# BluetoothHID.net
KiCad netlist of a schematic drawn in Altium Designer
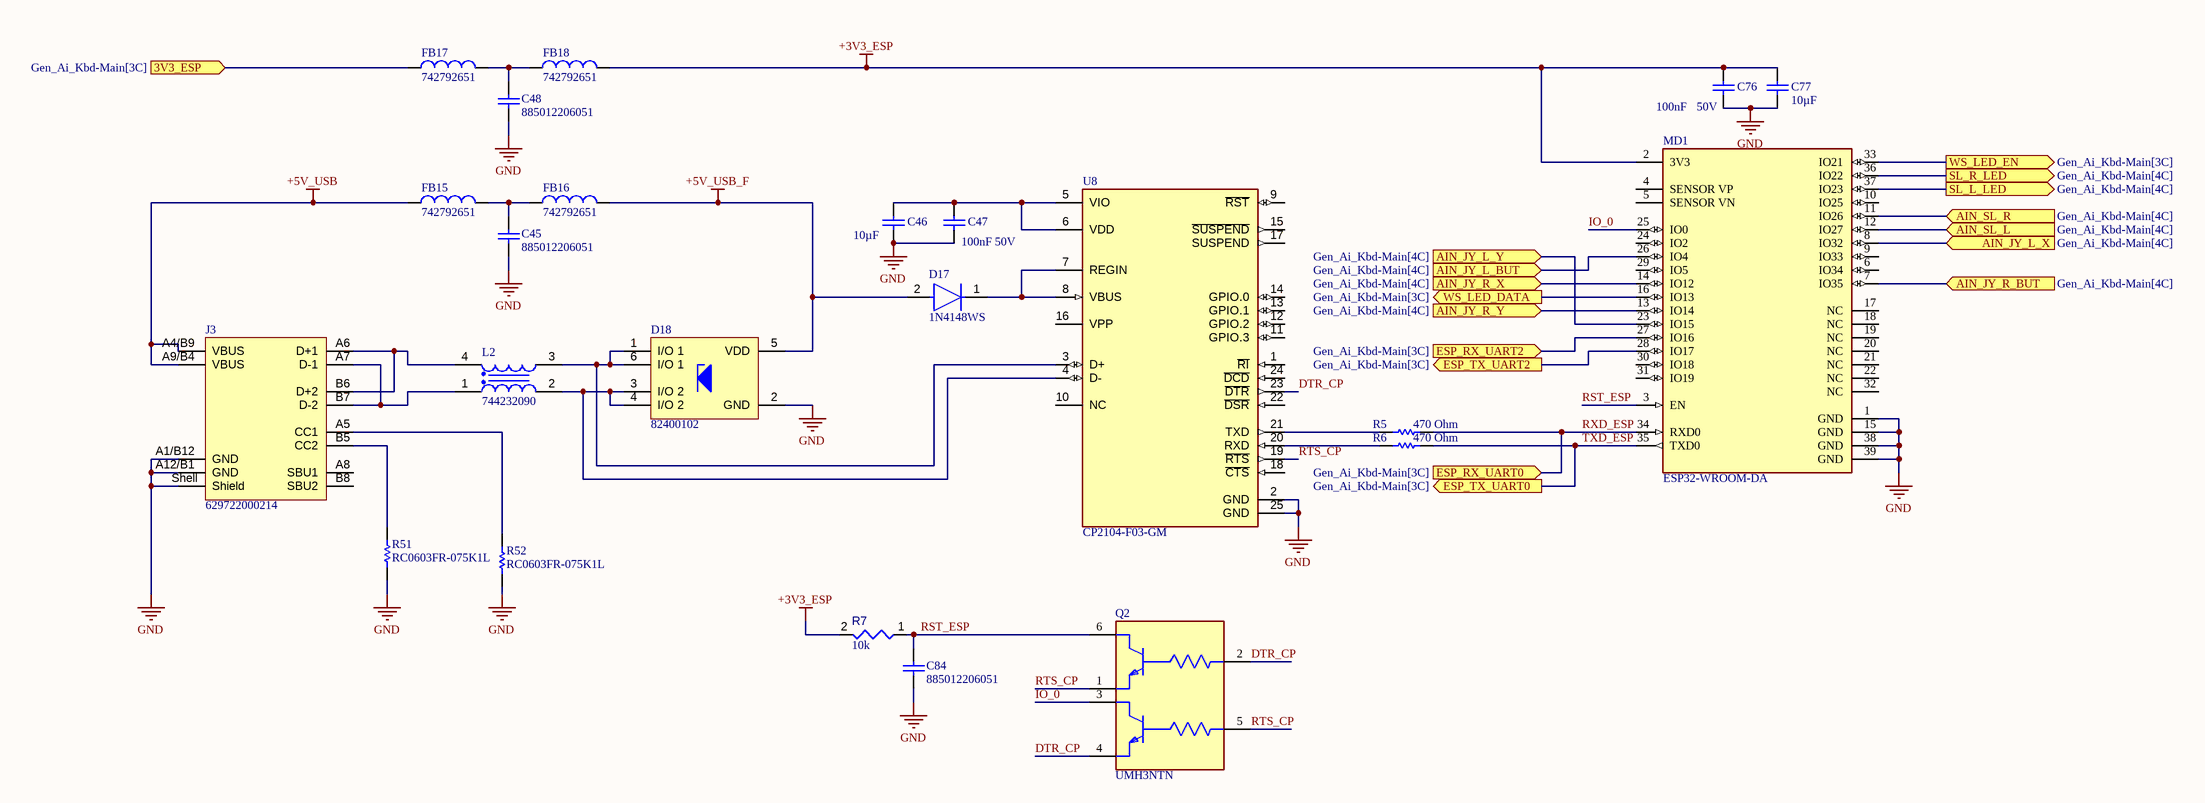
[diagram p0: BluetoothHID.SchDoc]

(export (version "E")
  (design (tool "Eeschema 10.0.6"))
  (components
    (comp (ref "C45")
      (value "885012206051")
      (footprint "WCAP-CSGP_0603_L1.6W0.8H0.8_Reflow")
      (description "885012206051 Cap Cer 0.68UF 16V X7R 0603")
      (fields (field (name "TOLERANCE") "10%"))
      (libsource (lib "Altium Content Vault") (part "Capacitor_Non-Polarized"))
    )
    (comp (ref "C46")
      (value "885012106006")
      (footprint "WCAP-CSGP_0603_L1.6W0.8H0.8_Reflow")
      (description "WCAP-CSGP Multilayer Ceramic Chip Capacitor, General Purpose, size 0603, X5R, 10µF, 6.3VDC")
      (fields (field (name "MANUFACTURER") "Wurth Elektronik") (field (name "CAPACITANCE") "10µF"))
      (libsource (lib "Test365") (part "885012209047R"))
    )
    (comp (ref "C47")
      (value "885012206095")
      (footprint "WCAP-CSGP_0603_L1.6W0.8H0.8_Reflow")
      (description "WCAP-CSGP Multilayer Ceramic Chip Capacitor, General Purpose, size 0603, X7R, 100nF, 50VDC")
      (fields
        (field (name "CAPACITANCE") "100nF")
        (field (name "MANUFACTURER") "Wurth Elektronik")
        (field (name "RATED VOLTAGE (DC)") "50V")
      )
      (libsource (lib "Test365") (part "885012209047R"))
    )
    (comp (ref "C48")
      (value "885012206051")
      (footprint "WCAP-CSGP_0603_L1.6W0.8H0.8_Reflow")
      (description "885012206051 Cap Cer 0.68UF 16V X7R 0603")
      (fields (field (name "TOLERANCE") "10%"))
      (libsource (lib "Altium Content Vault") (part "Capacitor_Non-Polarized"))
    )
    (comp (ref "C76")
      (value "885012206095")
      (footprint "WCAP-CSGP_0603_L1.6W0.8H0.8_Reflow")
      (description "WCAP-CSGP Multilayer Ceramic Chip Capacitor, General Purpose, size 0603, X7R, 100nF, 50VDC")
      (fields
        (field (name "CAPACITANCE") "100nF")
        (field (name "MANUFACTURER") "Wurth Elektronik")
        (field (name "RATED VOLTAGE (DC)") "50V")
      )
      (libsource (lib "Test365") (part "885012209047R"))
    )
    (comp (ref "C77")
      (value "885012106006")
      (footprint "WCAP-CSGP_0603_L1.6W0.8H0.8_Reflow")
      (description "WCAP-CSGP Multilayer Ceramic Chip Capacitor, General Purpose, size 0603, X5R, 10µF, 6.3VDC")
      (fields (field (name "MANUFACTURER") "Wurth Elektronik") (field (name "CAPACITANCE") "10µF"))
      (libsource (lib "Test365") (part "885012209047R"))
    )
    (comp (ref "C84")
      (value "885012206051")
      (footprint "WCAP-CSGP_0603_L1.6W0.8H0.8_Reflow")
      (description "885012206051 Cap Cer 0.68UF 16V X7R 0603")
      (fields (field (name "TOLERANCE") "10%"))
      (libsource (lib "Altium Content Vault") (part "Capacitor_Non-Polarized"))
    )
    (comp (ref "D17")
      (value "1N4148WS")
      (footprint "FP-477AB-IPC_C")
      (description "DIODE GEN PURP 75V 150MA SOD323F")
      (libsource (lib "Altium Content Vault") (part "d7152d700b627762746794eb795d46e"))
    )
    (comp (ref "D18")
      (value "82400102")
      (footprint "WE-TVS_SOT23-6L")
      (libsource (lib "Altium Content Vault") (part "Diode_2+1 Channel_Unidirectional - 82400102"))
    )
    (comp (ref "FB15")
      (value "742792651")
      (footprint "WE-CBF_0603_L1.6W0.8H0.8_HC")
      (fields (field (name "TOLERANCE") "25%"))
      (libsource (lib "Altium Content Vault") (part "Ferrite"))
    )
    (comp (ref "FB16")
      (value "742792651")
      (footprint "WE-CBF_0603_L1.6W0.8H0.8_HC")
      (fields (field (name "TOLERANCE") "25%"))
      (libsource (lib "Altium Content Vault") (part "Ferrite"))
    )
    (comp (ref "FB17")
      (value "742792651")
      (footprint "WE-CBF_0603_L1.6W0.8H0.8_HC")
      (fields (field (name "TOLERANCE") "25%"))
      (libsource (lib "Altium Content Vault") (part "Ferrite"))
    )
    (comp (ref "FB18")
      (value "742792651")
      (footprint "WE-CBF_0603_L1.6W0.8H0.8_HC")
      (fields (field (name "TOLERANCE") "25%"))
      (libsource (lib "Altium Content Vault") (part "Ferrite"))
    )
    (comp (ref "J3")
      (value "629722000214")
      (footprint "629722000214")
      (description "Conenctor USB 2.0 Type C Horizontal SMT")
      (libsource (lib "Altium Content Vault") (part "USB 2.0_Type C_Receptacle_1 Port_629722000214"))
    )
    (comp (ref "L2")
      (value "744232090")
      (footprint "WE-CNSW_1206")
      (fields (field (name "TOLERANCE") "25%"))
      (libsource (lib "Altium Content Vault") (part "WE-CNSW"))
    )
    (comp (ref "MD1")
      (value "ESP32-WROOM-DA")
      (footprint "FP-ESP32-WROOM-DA")
      (description "WiFi-Modul 802.11/BT 2, 4-2, 5GHz 150Mb/s, dual antenna")
      (libsource (lib "Test365") (part "7f842c3463a9561e2f6f9fdcd687e0f"))
    )
    (comp (ref "Q2")
      (value "UMH3NTN")
      (footprint "FP-UMT6-IPC_C")
      (description "TRANS 2NPN PREBIAS 0.15W UMT6")
      (libsource (lib "Altium Content Vault") (part "8b681bbdef8deb96797ed10fcd55d9e"))
    )
    (comp (ref "R5")
      (value "RC0603FR-07470RL")
      (footprint "RESC1608X55X25LL10T15")
      (fields (field (name "RESISTANCE") "470 Ohm"))
      (libsource (lib "Altium Content Vault") (part "RES-2"))
    )
    (comp (ref "R6")
      (value "RC0603FR-07470RL")
      (footprint "RESC1608X55X25LL10T15")
      (fields (field (name "RESISTANCE") "470 Ohm"))
      (libsource (lib "Altium Content Vault") (part "RES-2"))
    )
    (comp (ref "R7")
      (value "10k")
      (footprint "RESC1608X55X25ML10T15")
      (description "Chip Resistor, 10 KOhm, +/- 1%, 01 W, -55 to 155 degC, 0603 (1608 Metric)")
      (fields (field (name "POWER") "100mW") (field (name "TOLERANCE") "1%"))
      (libsource (lib "Test365") (part "RES-2"))
    )
    (comp (ref "R51")
      (value "RC0603FR-075K1L")
      (footprint "RESC1608X55X25ML10T15")
      (fields (field (name "MANUFACTURER") "Yageo"))
      (libsource (lib "Altium Content Vault") (part "RES"))
    )
    (comp (ref "R52")
      (value "RC0603FR-075K1L")
      (footprint "RESC1608X55X25ML10T15")
      (fields (field (name "MANUFACTURER") "Yageo"))
      (libsource (lib "Altium Content Vault") (part "RES"))
    )
    (comp (ref "U8")
      (value "CP2104-F03-GM")
      (footprint "FP-CP2104-F03-GM-MFG")
      (description "IC SGL USB-TO-UART BRIDGE 24QFN")
      (libsource (lib "Altium Content Vault") (part "36aa9e967c7f1036f799a443da3d357"))
    )
  )
  (nets
    (net (code "1") (name "+3V3_ESP") (class "Default")
      (node (ref "C76") (pin "2") (pinfunction "2_2") (pintype "passive"))
      (node (ref "C77") (pin "2") (pinfunction "2_2") (pintype "passive"))
      (node (ref "FB18") (pin "2") (pinfunction "2_2") (pintype "passive"))
      (node (ref "MD1") (pin "2") (pinfunction "3V3_2") (pintype "power_in"))
      (node (ref "R7") (pin "2") (pinfunction "2_2") (pintype "passive"))
    )
    (net (code "2") (name "+5V_USB") (class "Default")
      (node (ref "FB15") (pin "1") (pinfunction "1_1") (pintype "passive"))
      (node (ref "J3") (pin "A4/B9") (pinfunction "VBUS_A4/B9") (pintype "passive"))
      (node (ref "J3") (pin "A9/B4") (pinfunction "VBUS_A9/B4") (pintype "passive"))
    )
    (net (code "3") (name "+5V_USB_F") (class "Default")
      (node (ref "D17") (pin "2") (pinfunction "A_2") (pintype "passive"))
      (node (ref "D18") (pin "5") (pinfunction "VDD_5") (pintype "passive"))
      (node (ref "FB16") (pin "2") (pinfunction "2_2") (pintype "passive"))
    )
    (net (code "4") (name "/3V3_ESP") (class "Default")
      (node (ref "FB17") (pin "1") (pinfunction "1_1") (pintype "passive"))
    )
    (net (code "5") (name "/AIN_JY_L_BUT") (class "Default")
      (node (ref "MD1") (pin "26") (pinfunction "IO4_26") (pintype "bidirectional"))
    )
    (net (code "6") (name "/AIN_JY_L_X") (class "Default")
      (node (ref "MD1") (pin "8") (pinfunction "IO32_8") (pintype "bidirectional"))
    )
    (net (code "7") (name "/AIN_JY_L_Y") (class "Default")
      (node (ref "MD1") (pin "23") (pinfunction "IO15_23") (pintype "bidirectional"))
    )
    (net (code "8") (name "/AIN_JY_R_BUT") (class "Default")
      (node (ref "MD1") (pin "7") (pinfunction "IO35_7") (pintype "bidirectional"))
    )
    (net (code "9") (name "/AIN_JY_R_X") (class "Default")
      (node (ref "MD1") (pin "14") (pinfunction "IO12_14") (pintype "bidirectional"))
    )
    (net (code "10") (name "/AIN_JY_R_Y") (class "Default")
      (node (ref "MD1") (pin "13") (pinfunction "IO14_13") (pintype "bidirectional"))
    )
    (net (code "11") (name "/AIN_SL_L") (class "Default")
      (node (ref "MD1") (pin "12") (pinfunction "IO27_12") (pintype "bidirectional"))
    )
    (net (code "12") (name "/AIN_SL_R") (class "Default")
      (node (ref "MD1") (pin "11") (pinfunction "IO26_11") (pintype "bidirectional"))
    )
    (net (code "13") (name "/DTR_CP") (class "Default")
      (node (ref "Q2") (pin "2") (pinfunction "B_2") (pintype "passive"))
      (node (ref "Q2") (pin "4") (pinfunction "E_4") (pintype "passive"))
      (node (ref "U8") (pin "23") (pinfunction "~{DTR}_23") (pintype "output"))
    )
    (net (code "14") (name "/ESP_RX_UART2") (class "Default")
      (node (ref "MD1") (pin "27") (pinfunction "IO16_27") (pintype "bidirectional"))
    )
    (net (code "15") (name "/ESP_TX_UART2") (class "Default")
      (node (ref "MD1") (pin "28") (pinfunction "IO17_28") (pintype "bidirectional"))
    )
    (net (code "16") (name "/IO_0") (class "Default")
      (node (ref "MD1") (pin "25") (pinfunction "IO0_25") (pintype "bidirectional"))
      (node (ref "Q2") (pin "3") (pinfunction "C_3") (pintype "passive"))
    )
    (net (code "17") (name "/RST_ESP") (class "Default")
      (node (ref "C84") (pin "2") (pinfunction "2_2") (pintype "passive"))
      (node (ref "MD1") (pin "3") (pinfunction "EN_3") (pintype "input"))
      (node (ref "Q2") (pin "6") (pinfunction "C_6") (pintype "passive"))
      (node (ref "R7") (pin "1") (pinfunction "1_1") (pintype "passive"))
    )
    (net (code "18") (name "/RTS_CP") (class "Default")
      (node (ref "Q2") (pin "1") (pinfunction "E_1") (pintype "passive"))
      (node (ref "Q2") (pin "5") (pinfunction "B_5") (pintype "passive"))
      (node (ref "U8") (pin "19") (pinfunction "~{RTS}_19") (pintype "output"))
    )
    (net (code "19") (name "/RXD_ESP") (class "Default")
      (node (ref "MD1") (pin "34") (pinfunction "RXD0_34") (pintype "input"))
      (node (ref "R5") (pin "2") (pinfunction "2_2") (pintype "passive"))
    )
    (net (code "20") (name "/SL_L_LED") (class "Default")
      (node (ref "MD1") (pin "37") (pinfunction "IO23_37") (pintype "bidirectional"))
    )
    (net (code "21") (name "/SL_R_LED") (class "Default")
      (node (ref "MD1") (pin "36") (pinfunction "IO22_36") (pintype "bidirectional"))
    )
    (net (code "22") (name "/TXD_ESP") (class "Default")
      (node (ref "MD1") (pin "35") (pinfunction "TXD0_35") (pintype "output"))
      (node (ref "R6") (pin "2") (pinfunction "2_2") (pintype "passive"))
    )
    (net (code "23") (name "/WS_LED_DATA") (class "Default")
      (node (ref "MD1") (pin "16") (pinfunction "IO13_16") (pintype "bidirectional"))
    )
    (net (code "24") (name "/WS_LED_EN") (class "Default")
      (node (ref "MD1") (pin "33") (pinfunction "IO21_33") (pintype "bidirectional"))
    )
    (net (code "25") (name "GND") (class "Default")
      (node (ref "C45") (pin "1") (pinfunction "1_1") (pintype "passive"))
      (node (ref "C46") (pin "1") (pinfunction "1_1") (pintype "passive"))
      (node (ref "C47") (pin "1") (pinfunction "1_1") (pintype "passive"))
      (node (ref "C48") (pin "1") (pinfunction "1_1") (pintype "passive"))
      (node (ref "C76") (pin "1") (pinfunction "1_1") (pintype "passive"))
      (node (ref "C77") (pin "1") (pinfunction "1_1") (pintype "passive"))
      (node (ref "C84") (pin "1") (pinfunction "1_1") (pintype "passive"))
      (node (ref "D18") (pin "2") (pinfunction "GND_2") (pintype "passive"))
      (node (ref "J3") (pin "A1/B12") (pinfunction "GND_A1/B12") (pintype "passive"))
      (node (ref "J3") (pin "A12/B1") (pinfunction "GND_A12/B1") (pintype "passive"))
      (node (ref "J3") (pin "Shell") (pinfunction "Shield_Shell") (pintype "passive"))
      (node (ref "MD1") (pin "1") (pinfunction "GND_1") (pintype "power_in"))
      (node (ref "MD1") (pin "15") (pinfunction "GND_15") (pintype "power_in"))
      (node (ref "MD1") (pin "38") (pinfunction "GND_38") (pintype "power_in"))
      (node (ref "MD1") (pin "39") (pinfunction "GND_39") (pintype "power_in"))
      (node (ref "R51") (pin "1") (pinfunction "1_1") (pintype "passive"))
      (node (ref "R52") (pin "1") (pinfunction "1_1") (pintype "passive"))
      (node (ref "U8") (pin "2") (pinfunction "GND_2") (pintype "power_in"))
      (node (ref "U8") (pin "25") (pinfunction "GND_25") (pintype "power_in"))
    )
    (net (code "26") (name "Net-(C45-Pad2)") (class "Default")
      (node (ref "C45") (pin "2") (pinfunction "2_2") (pintype "passive"))
      (node (ref "FB15") (pin "2") (pinfunction "2_2") (pintype "passive"))
      (node (ref "FB16") (pin "1") (pinfunction "1_1") (pintype "passive"))
    )
    (net (code "27") (name "Net-(C48-Pad2)") (class "Default")
      (node (ref "C48") (pin "2") (pinfunction "2_2") (pintype "passive"))
      (node (ref "FB17") (pin "2") (pinfunction "2_2") (pintype "passive"))
      (node (ref "FB18") (pin "1") (pinfunction "1_1") (pintype "passive"))
    )
    (net (code "28") (name "Net-(D17-C)") (class "Default")
      (node (ref "D17") (pin "1") (pinfunction "C_1") (pintype "passive"))
      (node (ref "U8") (pin "7") (pinfunction "REGIN_7") (pintype "power_in"))
      (node (ref "U8") (pin "8") (pinfunction "VBUS_8") (pintype "input"))
    )
    (net (code "29") (name "Net-(J3-CC1)") (class "Default")
      (node (ref "J3") (pin "A5") (pinfunction "CC1_A5") (pintype "passive"))
      (node (ref "R52") (pin "2") (pinfunction "2_2") (pintype "passive"))
    )
    (net (code "30") (name "Net-(J3-CC2)") (class "Default")
      (node (ref "J3") (pin "B5") (pinfunction "CC2_B5") (pintype "passive"))
      (node (ref "R51") (pin "2") (pinfunction "2_2") (pintype "passive"))
    )
    (net (code "31") (name "Net-(J3-D+1)") (class "Default")
      (node (ref "J3") (pin "A6") (pinfunction "D+1_A6") (pintype "passive"))
      (node (ref "J3") (pin "B6") (pinfunction "D+2_B6") (pintype "passive"))
      (node (ref "L2") (pin "4") (pinfunction "4_4") (pintype "passive"))
    )
    (net (code "32") (name "Net-(J3-D-1)") (class "Default")
      (node (ref "J3") (pin "A7") (pinfunction "D-1_A7") (pintype "passive"))
      (node (ref "J3") (pin "B7") (pinfunction "D-2_B7") (pintype "passive"))
      (node (ref "L2") (pin "1") (pinfunction "1_1") (pintype "passive"))
    )
    (net (code "33") (name "Net-(U8-D+)") (class "Default")
      (node (ref "D18") (pin "1") (pinfunction "I/O_1_1") (pintype "passive"))
      (node (ref "D18") (pin "6") (pinfunction "I/O_1_6") (pintype "passive"))
      (node (ref "L2") (pin "3") (pinfunction "3_3") (pintype "passive"))
      (node (ref "U8") (pin "3") (pinfunction "D+_3") (pintype "bidirectional"))
    )
    (net (code "34") (name "Net-(U8-D-)") (class "Default")
      (node (ref "D18") (pin "3") (pinfunction "I/O_2_3") (pintype "passive"))
      (node (ref "D18") (pin "4") (pinfunction "I/O_2_4") (pintype "passive"))
      (node (ref "L2") (pin "2") (pinfunction "2_2") (pintype "passive"))
      (node (ref "U8") (pin "4") (pinfunction "D-_4") (pintype "bidirectional"))
    )
    (net (code "35") (name "Net-(U8-RXD)") (class "Default")
      (node (ref "R6") (pin "1") (pinfunction "1_1") (pintype "passive"))
      (node (ref "U8") (pin "20") (pinfunction "RXD_20") (pintype "input"))
    )
    (net (code "36") (name "Net-(U8-TXD)") (class "Default")
      (node (ref "R5") (pin "1") (pinfunction "1_1") (pintype "passive"))
      (node (ref "U8") (pin "21") (pinfunction "TXD_21") (pintype "output"))
    )
    (net (code "37") (name "Net-(U8-VDD)") (class "Default")
      (node (ref "C46") (pin "2") (pinfunction "2_2") (pintype "passive"))
      (node (ref "C47") (pin "2") (pinfunction "2_2") (pintype "passive"))
      (node (ref "U8") (pin "5") (pinfunction "VIO_5") (pintype "power_in"))
      (node (ref "U8") (pin "6") (pinfunction "VDD_6") (pintype "power_in"))
    )
    (net (code "38") (name "unconnected-(J3-SBU1-PadA8)") (class "Default")
      (node (ref "J3") (pin "A8") (pinfunction "SBU1_A8") (pintype "passive"))
    )
    (net (code "39") (name "unconnected-(J3-SBU2-PadB8)") (class "Default")
      (node (ref "J3") (pin "B8") (pinfunction "SBU2_B8") (pintype "passive"))
    )
    (net (code "40") (name "unconnected-(MD1-IO2-Pad24)") (class "Default")
      (node (ref "MD1") (pin "24") (pinfunction "IO2_24") (pintype "bidirectional"))
    )
    (net (code "41") (name "unconnected-(MD1-IO5-Pad29)") (class "Default")
      (node (ref "MD1") (pin "29") (pinfunction "IO5_29") (pintype "bidirectional"))
    )
    (net (code "42") (name "unconnected-(MD1-IO18-Pad30)") (class "Default")
      (node (ref "MD1") (pin "30") (pinfunction "IO18_30") (pintype "bidirectional"))
    )
    (net (code "43") (name "unconnected-(MD1-IO19-Pad31)") (class "Default")
      (node (ref "MD1") (pin "31") (pinfunction "IO19_31") (pintype "bidirectional"))
    )
    (net (code "44") (name "unconnected-(MD1-IO25-Pad10)") (class "Default")
      (node (ref "MD1") (pin "10") (pinfunction "IO25_10") (pintype "bidirectional"))
    )
    (net (code "45") (name "unconnected-(MD1-IO33-Pad9)") (class "Default")
      (node (ref "MD1") (pin "9") (pinfunction "IO33_9") (pintype "bidirectional"))
    )
    (net (code "46") (name "unconnected-(MD1-IO34-Pad6)") (class "Default")
      (node (ref "MD1") (pin "6") (pinfunction "IO34_6") (pintype "bidirectional"))
    )
    (net (code "47") (name "unconnected-(MD1-NC-Pad17)") (class "Default")
      (node (ref "MD1") (pin "17") (pinfunction "NC_17") (pintype "passive"))
    )
    (net (code "48") (name "unconnected-(MD1-NC-Pad18)") (class "Default")
      (node (ref "MD1") (pin "18") (pinfunction "NC_18") (pintype "passive"))
    )
    (net (code "49") (name "unconnected-(MD1-NC-Pad19)") (class "Default")
      (node (ref "MD1") (pin "19") (pinfunction "NC_19") (pintype "passive"))
    )
    (net (code "50") (name "unconnected-(MD1-NC-Pad20)") (class "Default")
      (node (ref "MD1") (pin "20") (pinfunction "NC_20") (pintype "passive"))
    )
    (net (code "51") (name "unconnected-(MD1-NC-Pad21)") (class "Default")
      (node (ref "MD1") (pin "21") (pinfunction "NC_21") (pintype "passive"))
    )
    (net (code "52") (name "unconnected-(MD1-NC-Pad22)") (class "Default")
      (node (ref "MD1") (pin "22") (pinfunction "NC_22") (pintype "passive"))
    )
    (net (code "53") (name "unconnected-(MD1-NC-Pad32)") (class "Default")
      (node (ref "MD1") (pin "32") (pinfunction "NC_32") (pintype "passive"))
    )
    (net (code "54") (name "unconnected-(MD1-SENSOR_VN-Pad5)") (class "Default")
      (node (ref "MD1") (pin "5") (pinfunction "SENSOR_VN_5") (pintype "passive"))
    )
    (net (code "55") (name "unconnected-(MD1-SENSOR_VP-Pad4)") (class "Default")
      (node (ref "MD1") (pin "4") (pinfunction "SENSOR_VP_4") (pintype "passive"))
    )
    (net (code "56") (name "unconnected-(U8-GPIO.0-Pad14)") (class "Default")
      (node (ref "U8") (pin "14") (pinfunction "GPIO.0_14") (pintype "bidirectional"))
    )
    (net (code "57") (name "unconnected-(U8-GPIO.1-Pad13)") (class "Default")
      (node (ref "U8") (pin "13") (pinfunction "GPIO.1_13") (pintype "bidirectional"))
    )
    (net (code "58") (name "unconnected-(U8-GPIO.2-Pad12)") (class "Default")
      (node (ref "U8") (pin "12") (pinfunction "GPIO.2_12") (pintype "bidirectional"))
    )
    (net (code "59") (name "unconnected-(U8-GPIO.3-Pad11)") (class "Default")
      (node (ref "U8") (pin "11") (pinfunction "GPIO.3_11") (pintype "bidirectional"))
    )
    (net (code "60") (name "unconnected-(U8-NC-Pad10)") (class "Default")
      (node (ref "U8") (pin "10") (pinfunction "NC_10") (pintype "passive"))
    )
    (net (code "61") (name "unconnected-(U8-SUSPEND-Pad17)") (class "Default")
      (node (ref "U8") (pin "17") (pinfunction "SUSPEND_17") (pintype "output"))
    )
    (net (code "62") (name "unconnected-(U8-VPP-Pad16)") (class "Default")
      (node (ref "U8") (pin "16") (pinfunction "VPP_16") (pintype "passive"))
    )
    (net (code "63") (name "unconnected-(U8-~{CTS}-Pad18)") (class "Default")
      (node (ref "U8") (pin "18") (pinfunction "~{CTS}_18") (pintype "input"))
    )
    (net (code "64") (name "unconnected-(U8-~{DCD}-Pad24)") (class "Default")
      (node (ref "U8") (pin "24") (pinfunction "~{DCD}_24") (pintype "input"))
    )
    (net (code "65") (name "unconnected-(U8-~{DSR}-Pad22)") (class "Default")
      (node (ref "U8") (pin "22") (pinfunction "~{DSR}_22") (pintype "input"))
    )
    (net (code "66") (name "unconnected-(U8-~{RI}-Pad1)") (class "Default")
      (node (ref "U8") (pin "1") (pinfunction "~{RI}_1") (pintype "input"))
    )
    (net (code "67") (name "unconnected-(U8-~{RST}-Pad9)") (class "Default")
      (node (ref "U8") (pin "9") (pinfunction "~{RST}_9") (pintype "bidirectional"))
    )
    (net (code "68") (name "unconnected-(U8-~{SUSPEND}-Pad15)") (class "Default")
      (node (ref "U8") (pin "15") (pinfunction "~{SUSPEND}_15") (pintype "output"))
    )
  )
)
